# FIT_HDMI_X19-9.net
KiCad netlist of a schematic drawn in Altium Designer
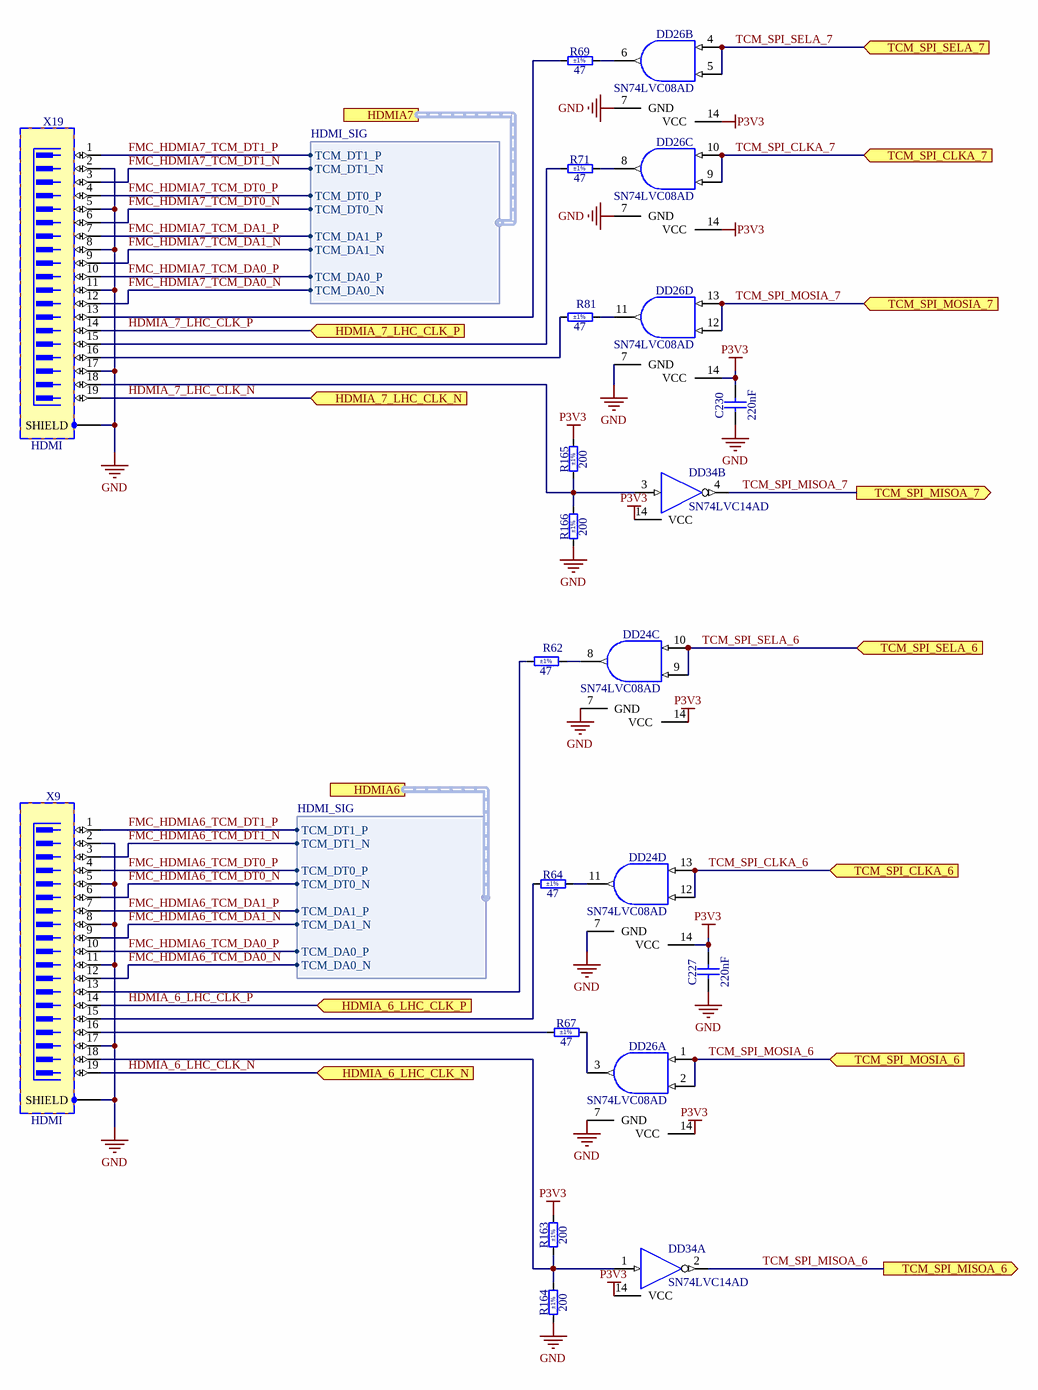
[diagram p0: FIT_HDMI_X19-9.SchDoc]

(export (version "E")
  (design (tool "Eeschema 10.0.6"))
  (components
    (comp (ref "C227")
      (value "220nF")
      (footprint "CAPC2012X135N")
      (description "Non-polarised capacitor")
      (fields
        (field (name "PART NUMBER") "CC0805_220NF_50V_10%_X7R")
        (field (name "VOLTAGE") "50V")
        (field (name "AUTHOR") "CERN DEM JLC")
      )
      (libsource (lib "Capacitors") (part "Capacitor - non polarized"))
    )
    (comp (ref "C230")
      (value "220nF")
      (footprint "CAPC2012X135N")
      (description "Non-polarised capacitor")
      (fields
        (field (name "PART NUMBER") "CC0805_220NF_50V_10%_X7R")
        (field (name "VOLTAGE") "50V")
        (field (name "AUTHOR") "CERN DEM JLC")
      )
      (libsource (lib "Capacitors") (part "Capacitor - non polarized"))
    )
    (comp (ref "DD24")
      (value "SN74LVC08AD")
      (footprint "SOIC127P600X175-14N")
      (description "Quad 2-Input AND Gate")
      (fields (field (name "MANUFACTURER") "TEXAS INSTRUMENTS") (field (name "AUTHOR") "CERN DEM JLC"))
      (libsource (lib "ICs And Semiconductors") (part "7408"))
    )
    (comp (ref "DD26")
      (value "SN74LVC08AD")
      (footprint "SOIC127P600X175-14N")
      (description "Quad 2-Input AND Gate")
      (fields (field (name "MANUFACTURER") "TEXAS INSTRUMENTS") (field (name "AUTHOR") "CERN DEM JLC"))
      (libsource (lib "ICs And Semiconductors") (part "7408"))
    )
    (comp (ref "DD34")
      (value "SN74LVC14AD")
      (footprint "SOIC127P600X175-14N")
      (description "Hex Schmitt-Trigger Inverter")
      (fields (field (name "MANUFACTURER") "TEXAS INSTRUMENTS") (field (name "AUTHOR") "CERN DEM JMW"))
      (libsource (lib "ICs And Semiconductors") (part "7414"))
    )
    (comp (ref "R62")
      (value "47")
      (footprint "RESC2012X60N")
      (description "Resistor - 1%")
      (fields
        (field (name "TOLERANCE") "±1%")
        (field (name "PART NUMBER") "R0805_47R_1%_0.125W_100PPM")
        (field (name "POWER") "0.125W")
        (field (name "AUTHOR") "CERN DEM JLC")
      )
      (libsource (lib "Resistors") (part "Resistor - 1%"))
    )
    (comp (ref "R64")
      (value "47")
      (footprint "RESC2012X60N")
      (description "Resistor - 1%")
      (fields
        (field (name "TOLERANCE") "±1%")
        (field (name "PART NUMBER") "R0805_47R_1%_0.125W_100PPM")
        (field (name "POWER") "0.125W")
        (field (name "AUTHOR") "CERN DEM JLC")
      )
      (libsource (lib "Resistors") (part "Resistor - 1%"))
    )
    (comp (ref "R67")
      (value "47")
      (footprint "RESC2012X60N")
      (description "Resistor - 1%")
      (fields
        (field (name "TOLERANCE") "±1%")
        (field (name "PART NUMBER") "R0805_47R_1%_0.125W_100PPM")
        (field (name "POWER") "0.125W")
        (field (name "AUTHOR") "CERN DEM JLC")
      )
      (libsource (lib "Resistors") (part "Resistor - 1%"))
    )
    (comp (ref "R69")
      (value "47")
      (footprint "RESC2012X60N")
      (description "Resistor - 1%")
      (fields
        (field (name "TOLERANCE") "±1%")
        (field (name "PART NUMBER") "R0805_47R_1%_0.125W_100PPM")
        (field (name "POWER") "0.125W")
        (field (name "AUTHOR") "CERN DEM JLC")
      )
      (libsource (lib "Resistors") (part "Resistor - 1%"))
    )
    (comp (ref "R71")
      (value "47")
      (footprint "RESC2012X60N")
      (description "Resistor - 1%")
      (fields
        (field (name "TOLERANCE") "±1%")
        (field (name "PART NUMBER") "R0805_47R_1%_0.125W_100PPM")
        (field (name "POWER") "0.125W")
        (field (name "AUTHOR") "CERN DEM JLC")
      )
      (libsource (lib "Resistors") (part "Resistor - 1%"))
    )
    (comp (ref "R81")
      (value "47")
      (footprint "RESC2012X60N")
      (description "Resistor - 1%")
      (fields
        (field (name "TOLERANCE") "±1%")
        (field (name "PART NUMBER") "R0805_47R_1%_0.125W_100PPM")
        (field (name "POWER") "0.125W")
        (field (name "AUTHOR") "CERN DEM JLC")
      )
      (libsource (lib "Resistors") (part "Resistor - 1%"))
    )
    (comp (ref "R163")
      (value "200")
      (footprint "RESC2012X60N")
      (description "Resistor - 1%")
      (fields
        (field (name "TOLERANCE") "±1%")
        (field (name "PART NUMBER") "R0805_200R_1%_0.125W_100PPM")
        (field (name "POWER") "0.125W")
        (field (name "AUTHOR") "CERN DEM JLC")
      )
      (libsource (lib "Resistors") (part "Resistor - 1%"))
    )
    (comp (ref "R164")
      (value "200")
      (footprint "RESC2012X60N")
      (description "Resistor - 1%")
      (fields
        (field (name "TOLERANCE") "±1%")
        (field (name "PART NUMBER") "R0805_200R_1%_0.125W_100PPM")
        (field (name "POWER") "0.125W")
        (field (name "AUTHOR") "CERN DEM JLC")
      )
      (libsource (lib "Resistors") (part "Resistor - 1%"))
    )
    (comp (ref "R165")
      (value "200")
      (footprint "RESC2012X60N")
      (description "Resistor - 1%")
      (fields
        (field (name "TOLERANCE") "±1%")
        (field (name "PART NUMBER") "R0805_200R_1%_0.125W_100PPM")
        (field (name "POWER") "0.125W")
        (field (name "AUTHOR") "CERN DEM JLC")
      )
      (libsource (lib "Resistors") (part "Resistor - 1%"))
    )
    (comp (ref "R166")
      (value "200")
      (footprint "RESC2012X60N")
      (description "Resistor - 1%")
      (fields
        (field (name "TOLERANCE") "±1%")
        (field (name "PART NUMBER") "R0805_200R_1%_0.125W_100PPM")
        (field (name "POWER") "0.125W")
        (field (name "AUTHOR") "CERN DEM JLC")
      )
      (libsource (lib "Resistors") (part "Resistor - 1%"))
    )
    (comp (ref "X9")
      (value "HDMI")
      (footprint "TYCO_2007435-1")
      (description "Connector HDMI 19 Male + 1 Shield")
      (fields
        (field (name "PART NUMBER") "TYCO_2007435-1")
        (field (name "MANUFACTURER") "TYCO ELECTRONICS")
        (field (name "AUTHOR") "CERN DEM MR")
      )
      (libsource (lib "Connectors") (part "Connector HDMI 19 Male + 1 Shield"))
    )
    (comp (ref "X19")
      (value "HDMI")
      (footprint "TYCO_2007435-1")
      (description "Connector HDMI 19 Male + 1 Shield")
      (fields
        (field (name "PART NUMBER") "TYCO_2007435-1")
        (field (name "MANUFACTURER") "TYCO ELECTRONICS")
        (field (name "AUTHOR") "CERN DEM MR")
      )
      (libsource (lib "Connectors") (part "Connector HDMI 19 Male + 1 Shield"))
    )
  )
  (nets
    (net (code "2") (name "/FMC_HDMIA6_TCM_DA0_N") (class "Default")
      (node (ref "X9") (pin "12") (pinfunction "12_12") (pintype "bidirectional"))
    )
    (net (code "3") (name "/FMC_HDMIA6_TCM_DA0_P") (class "Default")
      (node (ref "X9") (pin "10") (pinfunction "10_10") (pintype "bidirectional"))
    )
    (net (code "4") (name "/FMC_HDMIA6_TCM_DA1_N") (class "Default")
      (node (ref "X9") (pin "9") (pinfunction "9_9") (pintype "bidirectional"))
    )
    (net (code "5") (name "/FMC_HDMIA6_TCM_DA1_P") (class "Default")
      (node (ref "X9") (pin "7") (pinfunction "7_7") (pintype "bidirectional"))
    )
    (net (code "6") (name "/FMC_HDMIA6_TCM_DT0_N") (class "Default")
      (node (ref "X9") (pin "6") (pinfunction "6_6") (pintype "bidirectional"))
    )
    (net (code "7") (name "/FMC_HDMIA6_TCM_DT0_P") (class "Default")
      (node (ref "X9") (pin "4") (pinfunction "4_4") (pintype "bidirectional"))
    )
    (net (code "8") (name "/FMC_HDMIA6_TCM_DT1_N") (class "Default")
      (node (ref "X9") (pin "3") (pinfunction "3_3") (pintype "bidirectional"))
    )
    (net (code "9") (name "/FMC_HDMIA6_TCM_DT1_P") (class "Default")
      (node (ref "X9") (pin "1") (pinfunction "1_1") (pintype "bidirectional"))
    )
    (net (code "10") (name "/FMC_HDMIA7_TCM_DA0_N") (class "Default")
      (node (ref "X19") (pin "12") (pinfunction "12_12") (pintype "bidirectional"))
    )
    (net (code "11") (name "/FMC_HDMIA7_TCM_DA0_P") (class "Default")
      (node (ref "X19") (pin "10") (pinfunction "10_10") (pintype "bidirectional"))
    )
    (net (code "12") (name "/FMC_HDMIA7_TCM_DA1_N") (class "Default")
      (node (ref "X19") (pin "9") (pinfunction "9_9") (pintype "bidirectional"))
    )
    (net (code "13") (name "/FMC_HDMIA7_TCM_DA1_P") (class "Default")
      (node (ref "X19") (pin "7") (pinfunction "7_7") (pintype "bidirectional"))
    )
    (net (code "14") (name "/FMC_HDMIA7_TCM_DT0_N") (class "Default")
      (node (ref "X19") (pin "6") (pinfunction "6_6") (pintype "bidirectional"))
    )
    (net (code "15") (name "/FMC_HDMIA7_TCM_DT0_P") (class "Default")
      (node (ref "X19") (pin "4") (pinfunction "4_4") (pintype "bidirectional"))
    )
    (net (code "16") (name "/FMC_HDMIA7_TCM_DT1_N") (class "Default")
      (node (ref "X19") (pin "3") (pinfunction "3_3") (pintype "bidirectional"))
    )
    (net (code "17") (name "/FMC_HDMIA7_TCM_DT1_P") (class "Default")
      (node (ref "X19") (pin "1") (pinfunction "1_1") (pintype "bidirectional"))
    )
    (net (code "18") (name "/HDMIA_6_LHC_CLK_N") (class "Default")
      (node (ref "X9") (pin "19") (pinfunction "19_19") (pintype "bidirectional"))
    )
    (net (code "19") (name "/HDMIA_6_LHC_CLK_P") (class "Default")
      (node (ref "X9") (pin "14") (pinfunction "14_14") (pintype "bidirectional"))
    )
    (net (code "20") (name "/HDMIA_7_LHC_CLK_N") (class "Default")
      (node (ref "X19") (pin "19") (pinfunction "19_19") (pintype "bidirectional"))
    )
    (net (code "21") (name "/HDMIA_7_LHC_CLK_P") (class "Default")
      (node (ref "X19") (pin "14") (pinfunction "14_14") (pintype "bidirectional"))
    )
    (net (code "22") (name "/TCM_SPI_CLKA_6") (class "Default")
      (node (ref "DD24") (pin "12") (pinfunction "B_12") (pintype "input"))
      (node (ref "DD24") (pin "13") (pinfunction "A_13") (pintype "input"))
    )
    (net (code "23") (name "/TCM_SPI_CLKA_7") (class "Default")
      (node (ref "DD26") (pin "10") (pinfunction "A_10") (pintype "input"))
      (node (ref "DD26") (pin "9") (pinfunction "B_9") (pintype "input"))
    )
    (net (code "24") (name "/TCM_SPI_MISOA_6") (class "Default")
      (node (ref "DD34") (pin "2") (pinfunction "OUT_2") (pintype "output"))
    )
    (net (code "25") (name "/TCM_SPI_MISOA_7") (class "Default")
      (node (ref "DD34") (pin "4") (pinfunction "OUT_4") (pintype "output"))
    )
    (net (code "26") (name "/TCM_SPI_MOSIA_6") (class "Default")
      (node (ref "DD26") (pin "1") (pinfunction "A_1") (pintype "input"))
      (node (ref "DD26") (pin "2") (pinfunction "B_2") (pintype "input"))
    )
    (net (code "27") (name "/TCM_SPI_MOSIA_7") (class "Default")
      (node (ref "DD26") (pin "12") (pinfunction "B_12") (pintype "input"))
      (node (ref "DD26") (pin "13") (pinfunction "A_13") (pintype "input"))
    )
    (net (code "28") (name "/TCM_SPI_SELA_6") (class "Default")
      (node (ref "DD24") (pin "10") (pinfunction "A_10") (pintype "input"))
      (node (ref "DD24") (pin "9") (pinfunction "B_9") (pintype "input"))
    )
    (net (code "29") (name "/TCM_SPI_SELA_7") (class "Default")
      (node (ref "DD26") (pin "4") (pinfunction "A_4") (pintype "input"))
      (node (ref "DD26") (pin "5") (pinfunction "B_5") (pintype "input"))
    )
    (net (code "31") (name "GND") (class "Default")
      (node (ref "C227") (pin "1") (pinfunction "1_1") (pintype "passive"))
      (node (ref "C230") (pin "1") (pinfunction "1_1") (pintype "passive"))
      (node (ref "DD24") (pin "7") (pinfunction "GND_7") (pintype "power_in"))
      (node (ref "DD26") (pin "7") (pinfunction "GND_7") (pintype "power_in"))
      (node (ref "DD34") (pin "7") (pinfunction "GND_7") (pintype "power_in"))
      (node (ref "R164") (pin "1") (pinfunction "1_1") (pintype "passive"))
      (node (ref "R166") (pin "1") (pinfunction "1_1") (pintype "passive"))
      (node (ref "X19") (pin "11") (pinfunction "11_11") (pintype "bidirectional"))
      (node (ref "X19") (pin "17") (pinfunction "17_17") (pintype "bidirectional"))
      (node (ref "X19") (pin "2") (pinfunction "2_2") (pintype "bidirectional"))
      (node (ref "X19") (pin "5") (pinfunction "5_5") (pintype "bidirectional"))
      (node (ref "X19") (pin "8") (pinfunction "8_8") (pintype "bidirectional"))
      (node (ref "X19") (pin "SHIELD") (pinfunction "SHIELD_SHIELD") (pintype "power_in"))
      (node (ref "X9") (pin "11") (pinfunction "11_11") (pintype "bidirectional"))
      (node (ref "X9") (pin "17") (pinfunction "17_17") (pintype "bidirectional"))
      (node (ref "X9") (pin "2") (pinfunction "2_2") (pintype "bidirectional"))
      (node (ref "X9") (pin "5") (pinfunction "5_5") (pintype "bidirectional"))
      (node (ref "X9") (pin "8") (pinfunction "8_8") (pintype "bidirectional"))
      (node (ref "X9") (pin "SHIELD") (pinfunction "SHIELD_SHIELD") (pintype "power_in"))
    )
    (net (code "32") (name "Net-(DD24C-Y)") (class "Default")
      (node (ref "DD24") (pin "8") (pinfunction "Y_8") (pintype "output"))
      (node (ref "R62") (pin "2") (pinfunction "2_2") (pintype "passive"))
    )
    (net (code "33") (name "Net-(DD24D-Y)") (class "Default")
      (node (ref "DD24") (pin "11") (pinfunction "Y_11") (pintype "output"))
      (node (ref "R64") (pin "2") (pinfunction "2_2") (pintype "passive"))
    )
    (net (code "34") (name "Net-(DD26A-Y)") (class "Default")
      (node (ref "DD26") (pin "3") (pinfunction "Y_3") (pintype "output"))
      (node (ref "R67") (pin "2") (pinfunction "2_2") (pintype "passive"))
    )
    (net (code "35") (name "Net-(DD26B-Y)") (class "Default")
      (node (ref "DD26") (pin "6") (pinfunction "Y_6") (pintype "output"))
      (node (ref "R69") (pin "2") (pinfunction "2_2") (pintype "passive"))
    )
    (net (code "36") (name "Net-(DD26C-Y)") (class "Default")
      (node (ref "DD26") (pin "8") (pinfunction "Y_8") (pintype "output"))
      (node (ref "R71") (pin "2") (pinfunction "2_2") (pintype "passive"))
    )
    (net (code "37") (name "Net-(DD26D-Y)") (class "Default")
      (node (ref "DD26") (pin "11") (pinfunction "Y_11") (pintype "output"))
      (node (ref "R81") (pin "2") (pinfunction "2_2") (pintype "passive"))
    )
    (net (code "38") (name "Net-(DD34A-IN)") (class "Default")
      (node (ref "DD34") (pin "1") (pinfunction "IN_1") (pintype "input"))
      (node (ref "R163") (pin "1") (pinfunction "1_1") (pintype "passive"))
      (node (ref "R164") (pin "2") (pinfunction "2_2") (pintype "passive"))
      (node (ref "X9") (pin "18") (pinfunction "18_18") (pintype "bidirectional"))
    )
    (net (code "39") (name "Net-(DD34B-IN)") (class "Default")
      (node (ref "DD34") (pin "3") (pinfunction "IN_3") (pintype "input"))
      (node (ref "R165") (pin "1") (pinfunction "1_1") (pintype "passive"))
      (node (ref "R166") (pin "2") (pinfunction "2_2") (pintype "passive"))
      (node (ref "X19") (pin "18") (pinfunction "18_18") (pintype "bidirectional"))
    )
    (net (code "40") (name "Net-(R62-Pad1)") (class "Default")
      (node (ref "R62") (pin "1") (pinfunction "1_1") (pintype "passive"))
      (node (ref "X9") (pin "13") (pinfunction "13_13") (pintype "bidirectional"))
    )
    (net (code "41") (name "Net-(R64-Pad1)") (class "Default")
      (node (ref "R64") (pin "1") (pinfunction "1_1") (pintype "passive"))
      (node (ref "X9") (pin "15") (pinfunction "15_15") (pintype "bidirectional"))
    )
    (net (code "42") (name "Net-(R67-Pad1)") (class "Default")
      (node (ref "R67") (pin "1") (pinfunction "1_1") (pintype "passive"))
      (node (ref "X9") (pin "16") (pinfunction "16_16") (pintype "bidirectional"))
    )
    (net (code "43") (name "Net-(R69-Pad1)") (class "Default")
      (node (ref "R69") (pin "1") (pinfunction "1_1") (pintype "passive"))
      (node (ref "X19") (pin "13") (pinfunction "13_13") (pintype "bidirectional"))
    )
    (net (code "44") (name "Net-(R71-Pad1)") (class "Default")
      (node (ref "R71") (pin "1") (pinfunction "1_1") (pintype "passive"))
      (node (ref "X19") (pin "15") (pinfunction "15_15") (pintype "bidirectional"))
    )
    (net (code "45") (name "Net-(R81-Pad1)") (class "Default")
      (node (ref "R81") (pin "1") (pinfunction "1_1") (pintype "passive"))
      (node (ref "X19") (pin "16") (pinfunction "16_16") (pintype "bidirectional"))
    )
    (net (code "46") (name "P3V3") (class "Default")
      (node (ref "C227") (pin "2") (pinfunction "2_2") (pintype "passive"))
      (node (ref "C230") (pin "2") (pinfunction "2_2") (pintype "passive"))
      (node (ref "DD24") (pin "14") (pinfunction "VCC_14") (pintype "power_in"))
      (node (ref "DD26") (pin "14") (pinfunction "VCC_14") (pintype "power_in"))
      (node (ref "DD34") (pin "14") (pinfunction "VCC_14") (pintype "power_in"))
      (node (ref "R163") (pin "2") (pinfunction "2_2") (pintype "passive"))
      (node (ref "R165") (pin "2") (pinfunction "2_2") (pintype "passive"))
    )
  )
)
